# Standalone_Kaleidoscope_8085_LED_BOARD_V.net
KiCad netlist of a schematic drawn in EAGLE
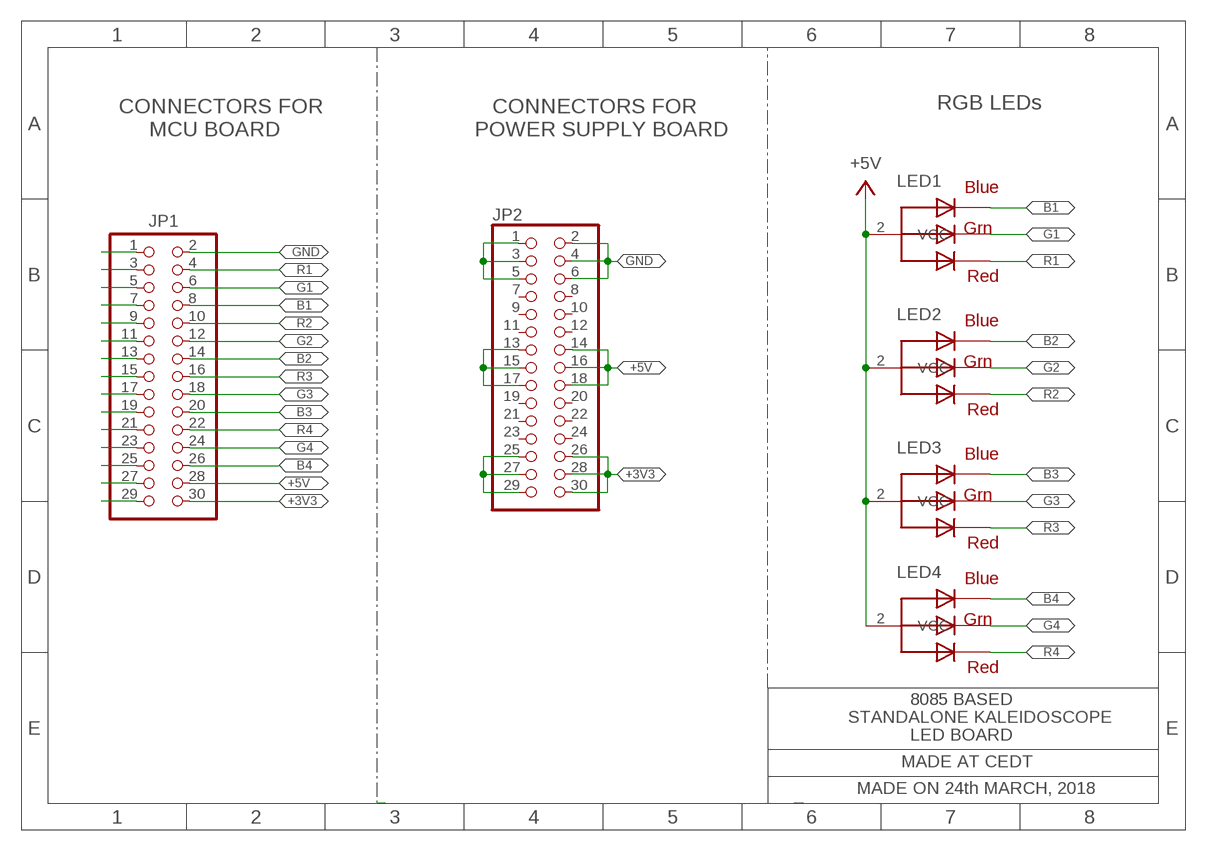
[diagram p0: schematic, sheet 1]

(export (version "E")
  (design (tool "Eeschema 10.0.6"))
  (components
    (comp (ref "JP1")
      (value "PINHD-2X15")
      (footprint "eagle-import:2X15")
      (libsource (lib "eagle-import") (part "PINHD-2X15"))
    )
    (comp (ref "JP2")
      (value "PINHD-2X15")
      (footprint "eagle-import:2X15")
      (libsource (lib "eagle-import") (part "PINHD-2X15"))
    )
    (comp (ref "LED1")
      (value "RGBLED_CA")
      (footprint "eagle-import:LED5MMRGB")
      (libsource (lib "eagle-import") (part "RGBLED_CA"))
    )
    (comp (ref "LED2")
      (value "RGBLED_CA")
      (footprint "eagle-import:LED5MMRGB")
      (libsource (lib "eagle-import") (part "RGBLED_CA"))
    )
    (comp (ref "LED3")
      (value "RGBLED_CA")
      (footprint "eagle-import:LED5MMRGB")
      (libsource (lib "eagle-import") (part "RGBLED_CA"))
    )
    (comp (ref "LED4")
      (value "RGBLED_CA")
      (footprint "eagle-import:LED5MMRGB")
      (libsource (lib "eagle-import") (part "RGBLED_CA"))
    )
  )
  (nets
    (net (code "1") (name "+5V") (class "Default")
      (node (ref "JP1") (pin "27") (pinfunction "27_27") (pintype "passive"))
      (node (ref "JP1") (pin "28") (pinfunction "28_28") (pintype "passive"))
      (node (ref "JP2") (pin "13") (pinfunction "13_13") (pintype "passive"))
      (node (ref "JP2") (pin "14") (pinfunction "14_14") (pintype "passive"))
      (node (ref "JP2") (pin "15") (pinfunction "15_15") (pintype "passive"))
      (node (ref "JP2") (pin "16") (pinfunction "16_16") (pintype "passive"))
      (node (ref "JP2") (pin "17") (pinfunction "17_17") (pintype "passive"))
      (node (ref "JP2") (pin "18") (pinfunction "18_18") (pintype "passive"))
      (node (ref "LED1") (pin "2") (pinfunction "VCC_2") (pintype "bidirectional"))
      (node (ref "LED2") (pin "2") (pinfunction "VCC_2") (pintype "bidirectional"))
      (node (ref "LED3") (pin "2") (pinfunction "VCC_2") (pintype "bidirectional"))
      (node (ref "LED4") (pin "2") (pinfunction "VCC_2") (pintype "bidirectional"))
    )
    (net (code "2") (name "/+3V3") (class "Default")
      (node (ref "JP1") (pin "29") (pinfunction "29_29") (pintype "passive"))
      (node (ref "JP1") (pin "30") (pinfunction "30_30") (pintype "passive"))
      (node (ref "JP2") (pin "25") (pinfunction "25_25") (pintype "passive"))
      (node (ref "JP2") (pin "26") (pinfunction "26_26") (pintype "passive"))
      (node (ref "JP2") (pin "27") (pinfunction "27_27") (pintype "passive"))
      (node (ref "JP2") (pin "28") (pinfunction "28_28") (pintype "passive"))
      (node (ref "JP2") (pin "29") (pinfunction "29_29") (pintype "passive"))
      (node (ref "JP2") (pin "30") (pinfunction "30_30") (pintype "passive"))
    )
    (net (code "3") (name "/B1") (class "Default")
      (node (ref "JP1") (pin "7") (pinfunction "7_7") (pintype "passive"))
      (node (ref "JP1") (pin "8") (pinfunction "8_8") (pintype "passive"))
      (node (ref "LED1") (pin "4") (pinfunction "BLUE_4") (pintype "bidirectional"))
    )
    (net (code "4") (name "/B2") (class "Default")
      (node (ref "JP1") (pin "13") (pinfunction "13_13") (pintype "passive"))
      (node (ref "JP1") (pin "14") (pinfunction "14_14") (pintype "passive"))
      (node (ref "LED2") (pin "4") (pinfunction "BLUE_4") (pintype "bidirectional"))
    )
    (net (code "5") (name "/B3") (class "Default")
      (node (ref "JP1") (pin "19") (pinfunction "19_19") (pintype "passive"))
      (node (ref "JP1") (pin "20") (pinfunction "20_20") (pintype "passive"))
      (node (ref "LED3") (pin "4") (pinfunction "BLUE_4") (pintype "bidirectional"))
    )
    (net (code "6") (name "/B4") (class "Default")
      (node (ref "JP1") (pin "25") (pinfunction "25_25") (pintype "passive"))
      (node (ref "JP1") (pin "26") (pinfunction "26_26") (pintype "passive"))
      (node (ref "LED4") (pin "4") (pinfunction "BLUE_4") (pintype "bidirectional"))
    )
    (net (code "7") (name "/G1") (class "Default")
      (node (ref "JP1") (pin "5") (pinfunction "5_5") (pintype "passive"))
      (node (ref "JP1") (pin "6") (pinfunction "6_6") (pintype "passive"))
      (node (ref "LED1") (pin "3") (pinfunction "GREEN_3") (pintype "bidirectional"))
    )
    (net (code "8") (name "/G2") (class "Default")
      (node (ref "JP1") (pin "11") (pinfunction "11_11") (pintype "passive"))
      (node (ref "JP1") (pin "12") (pinfunction "12_12") (pintype "passive"))
      (node (ref "LED2") (pin "3") (pinfunction "GREEN_3") (pintype "bidirectional"))
    )
    (net (code "9") (name "/G3") (class "Default")
      (node (ref "JP1") (pin "17") (pinfunction "17_17") (pintype "passive"))
      (node (ref "JP1") (pin "18") (pinfunction "18_18") (pintype "passive"))
      (node (ref "LED3") (pin "3") (pinfunction "GREEN_3") (pintype "bidirectional"))
    )
    (net (code "10") (name "/G4") (class "Default")
      (node (ref "JP1") (pin "23") (pinfunction "23_23") (pintype "passive"))
      (node (ref "JP1") (pin "24") (pinfunction "24_24") (pintype "passive"))
      (node (ref "LED4") (pin "3") (pinfunction "GREEN_3") (pintype "bidirectional"))
    )
    (net (code "11") (name "/GND") (class "Default")
      (node (ref "JP1") (pin "1") (pinfunction "1_1") (pintype "passive"))
      (node (ref "JP1") (pin "2") (pinfunction "2_2") (pintype "passive"))
      (node (ref "JP2") (pin "1") (pinfunction "1_1") (pintype "passive"))
      (node (ref "JP2") (pin "2") (pinfunction "2_2") (pintype "passive"))
      (node (ref "JP2") (pin "3") (pinfunction "3_3") (pintype "passive"))
      (node (ref "JP2") (pin "4") (pinfunction "4_4") (pintype "passive"))
      (node (ref "JP2") (pin "5") (pinfunction "5_5") (pintype "passive"))
      (node (ref "JP2") (pin "6") (pinfunction "6_6") (pintype "passive"))
    )
    (net (code "12") (name "/R1") (class "Default")
      (node (ref "JP1") (pin "3") (pinfunction "3_3") (pintype "passive"))
      (node (ref "JP1") (pin "4") (pinfunction "4_4") (pintype "passive"))
      (node (ref "LED1") (pin "1") (pinfunction "RED_1") (pintype "bidirectional"))
    )
    (net (code "13") (name "/R2") (class "Default")
      (node (ref "JP1") (pin "10") (pinfunction "10_10") (pintype "passive"))
      (node (ref "JP1") (pin "9") (pinfunction "9_9") (pintype "passive"))
      (node (ref "LED2") (pin "1") (pinfunction "RED_1") (pintype "bidirectional"))
    )
    (net (code "14") (name "/R3") (class "Default")
      (node (ref "JP1") (pin "15") (pinfunction "15_15") (pintype "passive"))
      (node (ref "JP1") (pin "16") (pinfunction "16_16") (pintype "passive"))
      (node (ref "LED3") (pin "1") (pinfunction "RED_1") (pintype "bidirectional"))
    )
    (net (code "15") (name "/R4") (class "Default")
      (node (ref "JP1") (pin "21") (pinfunction "21_21") (pintype "passive"))
      (node (ref "JP1") (pin "22") (pinfunction "22_22") (pintype "passive"))
      (node (ref "LED4") (pin "1") (pinfunction "RED_1") (pintype "bidirectional"))
    )
    (net (code "16") (name "unconnected-(JP2-Pad7)") (class "Default")
      (node (ref "JP2") (pin "7") (pinfunction "7_7") (pintype "passive"))
    )
    (net (code "17") (name "unconnected-(JP2-Pad8)") (class "Default")
      (node (ref "JP2") (pin "8") (pinfunction "8_8") (pintype "passive"))
    )
    (net (code "18") (name "unconnected-(JP2-Pad9)") (class "Default")
      (node (ref "JP2") (pin "9") (pinfunction "9_9") (pintype "passive"))
    )
    (net (code "19") (name "unconnected-(JP2-Pad10)") (class "Default")
      (node (ref "JP2") (pin "10") (pinfunction "10_10") (pintype "passive"))
    )
    (net (code "20") (name "unconnected-(JP2-Pad11)") (class "Default")
      (node (ref "JP2") (pin "11") (pinfunction "11_11") (pintype "passive"))
    )
    (net (code "21") (name "unconnected-(JP2-Pad12)") (class "Default")
      (node (ref "JP2") (pin "12") (pinfunction "12_12") (pintype "passive"))
    )
    (net (code "22") (name "unconnected-(JP2-Pad19)") (class "Default")
      (node (ref "JP2") (pin "19") (pinfunction "19_19") (pintype "passive"))
    )
    (net (code "23") (name "unconnected-(JP2-Pad20)") (class "Default")
      (node (ref "JP2") (pin "20") (pinfunction "20_20") (pintype "passive"))
    )
    (net (code "24") (name "unconnected-(JP2-Pad21)") (class "Default")
      (node (ref "JP2") (pin "21") (pinfunction "21_21") (pintype "passive"))
    )
    (net (code "25") (name "unconnected-(JP2-Pad22)") (class "Default")
      (node (ref "JP2") (pin "22") (pinfunction "22_22") (pintype "passive"))
    )
    (net (code "26") (name "unconnected-(JP2-Pad23)") (class "Default")
      (node (ref "JP2") (pin "23") (pinfunction "23_23") (pintype "passive"))
    )
    (net (code "27") (name "unconnected-(JP2-Pad24)") (class "Default")
      (node (ref "JP2") (pin "24") (pinfunction "24_24") (pintype "passive"))
    )
  )
)
